# pcb.net
KiCad netlist of a schematic drawn in EAGLE
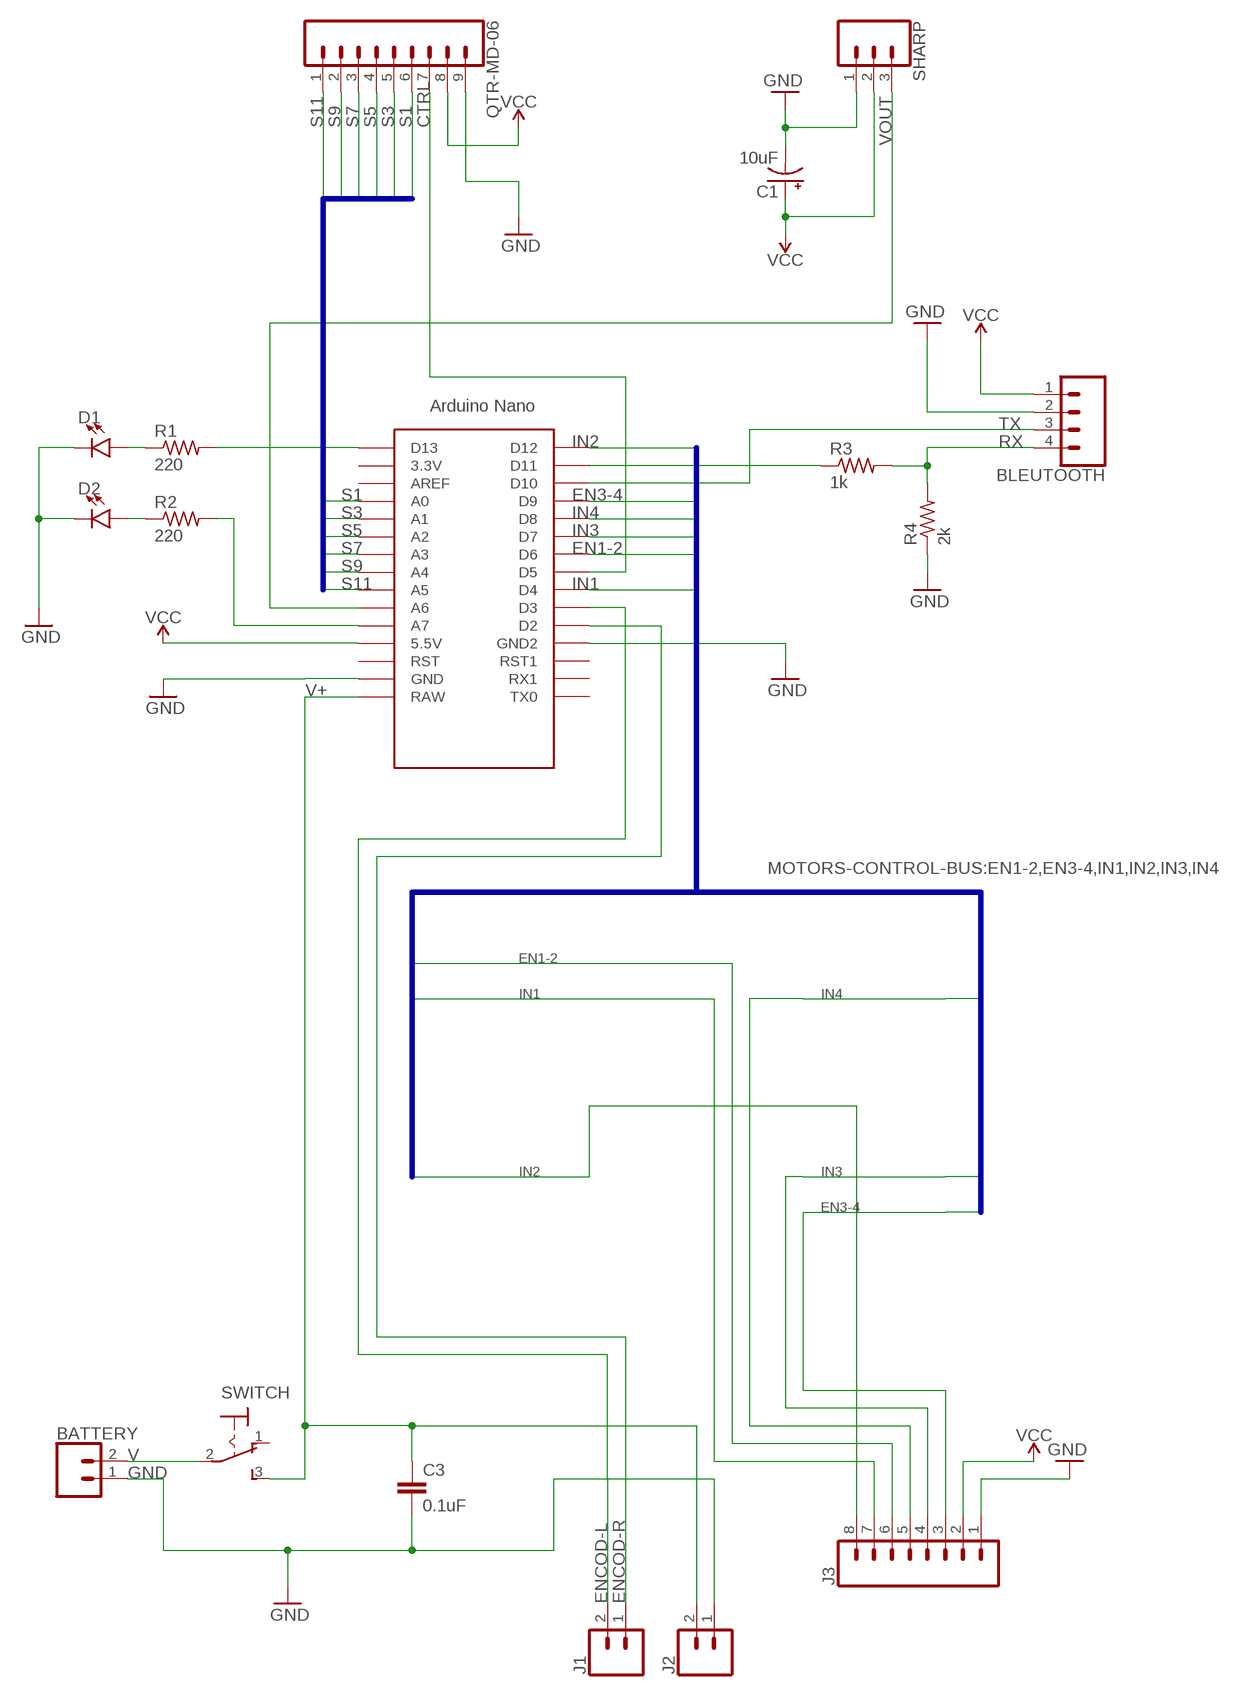
[diagram p0: schematic, sheet 1]

(export (version "E")
  (design (tool "Eeschema 10.0.6"))
  (components
    (comp (ref "BATTERY")
      (value "CONN_02")
      (footprint "eagle-import:1X02")
      (libsource (lib "eagle-import") (part "CONN_02"))
    )
    (comp (ref "BLEUTOOTH")
      (value "CONN_04")
      (footprint "eagle-import:1X04")
      (libsource (lib "eagle-import") (part "CONN_04"))
    )
    (comp (ref "C1")
      (value "10uF")
      (footprint "eagle-import:CPOL-RADIAL-2.5MM-5MM")
      (libsource (lib "eagle-import") (part "10UF-POLAR-RADIAL-2.5MM-25V-20%"))
    )
    (comp (ref "C3")
      (value "0.1uF")
      (footprint "eagle-import:CAP-PTH-SMALL-KIT")
      (libsource (lib "eagle-import") (part "0.1UF-KIT-EZ-50V-20%"))
    )
    (comp (ref "D1")
      (value "LED3MM")
      (footprint "eagle-import:LED_3MM")
      (libsource (lib "eagle-import") (part "LED3MM"))
    )
    (comp (ref "D2")
      (value "LED3MM")
      (footprint "eagle-import:LED_3MM")
      (libsource (lib "eagle-import") (part "LED3MM"))
    )
    (comp (ref "J1")
      (value "CONN_025MM")
      (footprint "eagle-import:SCREWTERMINAL-5MM-2")
      (libsource (lib "eagle-import") (part "CONN_025MM"))
    )
    (comp (ref "J2")
      (value "CONN_025MM")
      (footprint "eagle-import:SCREWTERMINAL-5MM-2")
      (libsource (lib "eagle-import") (part "CONN_025MM"))
    )
    (comp (ref "J3")
      (value "CONN_08\"")
      (footprint "eagle-import:1X08")
      (libsource (lib "eagle-import") (part "CONN_08{dblquote}"))
    )
    (comp (ref "QTR-MD-06")
      (value "CONN_09")
      (footprint "eagle-import:1X09")
      (libsource (lib "eagle-import") (part "CONN_09"))
    )
    (comp (ref "R1")
      (value "220")
      (footprint "eagle-import:0207_12")
      (libsource (lib "eagle-import") (part "R-US_0207/12"))
    )
    (comp (ref "R2")
      (value "220")
      (footprint "eagle-import:0207_12")
      (libsource (lib "eagle-import") (part "R-US_0207/12"))
    )
    (comp (ref "R3")
      (value "1k")
      (footprint "eagle-import:0207_12")
      (libsource (lib "eagle-import") (part "R-US_0207/12"))
    )
    (comp (ref "R4")
      (value "2k")
      (footprint "eagle-import:0207_12")
      (libsource (lib "eagle-import") (part "R-US_0207/12"))
    )
    (comp (ref "SHARP")
      (value "CONN_03")
      (footprint "eagle-import:1X03")
      (libsource (lib "eagle-import") (part "CONN_03"))
    )
    (comp (ref "SWITCH")
      (value "320-916")
      (footprint "eagle-import:320-916")
      (libsource (lib "eagle-import") (part "320-916"))
    )
    (comp (ref "U$1")
      (value "NANO")
      (footprint "eagle-import:NANO")
      (libsource (lib "eagle-import") (part "NANO"))
    )
  )
  (nets
    (net (code "2") (name "/CTRL") (class "Default")
      (node (ref "QTR-MD-06") (pin "7") (pinfunction "7_7") (pintype "passive"))
      (node (ref "U$1") (pin "D5") (pinfunction "D5_D5") (pintype "bidirectional"))
    )
    (net (code "3") (name "/EN1-2") (class "Default")
      (node (ref "J3") (pin "6") (pinfunction "6_6") (pintype "passive"))
      (node (ref "U$1") (pin "D6") (pinfunction "D6_D6") (pintype "bidirectional"))
    )
    (net (code "4") (name "/EN3-4") (class "Default")
      (node (ref "J3") (pin "3") (pinfunction "3_3") (pintype "passive"))
      (node (ref "U$1") (pin "D9") (pinfunction "D9_D9") (pintype "bidirectional"))
    )
    (net (code "5") (name "/ENCOD-L") (class "Default")
      (node (ref "J1") (pin "2") (pinfunction "2_2") (pintype "passive"))
      (node (ref "U$1") (pin "D3") (pinfunction "D3_D3") (pintype "bidirectional"))
    )
    (net (code "6") (name "/ENCOD-R") (class "Default")
      (node (ref "J1") (pin "1") (pinfunction "1_1") (pintype "passive"))
      (node (ref "U$1") (pin "D2") (pinfunction "D2_D2") (pintype "bidirectional"))
    )
    (net (code "7") (name "/IN1") (class "Default")
      (node (ref "J3") (pin "7") (pinfunction "7_7") (pintype "passive"))
      (node (ref "U$1") (pin "D4") (pinfunction "D4_D4") (pintype "bidirectional"))
    )
    (net (code "8") (name "/IN2") (class "Default")
      (node (ref "J3") (pin "8") (pinfunction "8_8") (pintype "passive"))
      (node (ref "U$1") (pin "D12") (pinfunction "D12_D12") (pintype "bidirectional"))
    )
    (net (code "9") (name "/IN3") (class "Default")
      (node (ref "J3") (pin "4") (pinfunction "4_4") (pintype "passive"))
      (node (ref "U$1") (pin "D7") (pinfunction "D7_D7") (pintype "bidirectional"))
    )
    (net (code "10") (name "/IN4") (class "Default")
      (node (ref "J3") (pin "5") (pinfunction "5_5") (pintype "passive"))
      (node (ref "U$1") (pin "D8") (pinfunction "D8_D8") (pintype "bidirectional"))
    )
    (net (code "11") (name "/RX") (class "Default")
      (node (ref "BLEUTOOTH") (pin "4") (pinfunction "4_4") (pintype "passive"))
      (node (ref "R3") (pin "2") (pinfunction "2_2") (pintype "passive"))
      (node (ref "R4") (pin "2") (pinfunction "2_2") (pintype "passive"))
    )
    (net (code "12") (name "/S1") (class "Default")
      (node (ref "QTR-MD-06") (pin "6") (pinfunction "6_6") (pintype "passive"))
      (node (ref "U$1") (pin "A0") (pinfunction "A0_A0") (pintype "bidirectional"))
    )
    (net (code "13") (name "/S3") (class "Default")
      (node (ref "QTR-MD-06") (pin "5") (pinfunction "5_5") (pintype "passive"))
      (node (ref "U$1") (pin "A1") (pinfunction "A1_A1") (pintype "bidirectional"))
    )
    (net (code "14") (name "/S5") (class "Default")
      (node (ref "QTR-MD-06") (pin "4") (pinfunction "4_4") (pintype "passive"))
      (node (ref "U$1") (pin "A2") (pinfunction "A2_A2") (pintype "bidirectional"))
    )
    (net (code "15") (name "/S7") (class "Default")
      (node (ref "QTR-MD-06") (pin "3") (pinfunction "3_3") (pintype "passive"))
      (node (ref "U$1") (pin "A3") (pinfunction "A3_A3") (pintype "bidirectional"))
    )
    (net (code "16") (name "/S9") (class "Default")
      (node (ref "QTR-MD-06") (pin "2") (pinfunction "2_2") (pintype "passive"))
      (node (ref "U$1") (pin "A4") (pinfunction "A4_A4") (pintype "bidirectional"))
    )
    (net (code "17") (name "/S11") (class "Default")
      (node (ref "QTR-MD-06") (pin "1") (pinfunction "1_1") (pintype "passive"))
      (node (ref "U$1") (pin "A5") (pinfunction "A5_A5") (pintype "bidirectional"))
    )
    (net (code "18") (name "/TX") (class "Default")
      (node (ref "BLEUTOOTH") (pin "3") (pinfunction "3_3") (pintype "passive"))
      (node (ref "U$1") (pin "D10") (pinfunction "D10_D10") (pintype "bidirectional"))
    )
    (net (code "19") (name "/V") (class "Default")
      (node (ref "BATTERY") (pin "2") (pinfunction "2_2") (pintype "passive"))
      (node (ref "SWITCH") (pin "2") (pinfunction "P_2") (pintype "passive"))
    )
    (net (code "20") (name "/V+") (class "Default")
      (node (ref "C3") (pin "1") (pinfunction "1_1") (pintype "passive"))
      (node (ref "J2") (pin "2") (pinfunction "2_2") (pintype "passive"))
      (node (ref "SWITCH") (pin "3") (pinfunction "S_3") (pintype "passive"))
      (node (ref "U$1") (pin "RAW") (pinfunction "RAW_RAW") (pintype "bidirectional"))
    )
    (net (code "21") (name "/VOUT") (class "Default")
      (node (ref "SHARP") (pin "3") (pinfunction "3_3") (pintype "passive"))
      (node (ref "U$1") (pin "A6") (pinfunction "A6_A6") (pintype "bidirectional"))
    )
    (net (code "23") (name "GND") (class "Default")
      (node (ref "BATTERY") (pin "1") (pinfunction "1_1") (pintype "passive"))
      (node (ref "BLEUTOOTH") (pin "2") (pinfunction "2_2") (pintype "passive"))
      (node (ref "C1") (pin "2") (pinfunction "-_2") (pintype "passive"))
      (node (ref "C3") (pin "2") (pinfunction "2_2") (pintype "passive"))
      (node (ref "D1") (pin "K") (pinfunction "C_K") (pintype "passive"))
      (node (ref "D2") (pin "K") (pinfunction "C_K") (pintype "passive"))
      (node (ref "J2") (pin "1") (pinfunction "1_1") (pintype "passive"))
      (node (ref "J3") (pin "1") (pinfunction "1_1") (pintype "passive"))
      (node (ref "QTR-MD-06") (pin "9") (pinfunction "9_9") (pintype "passive"))
      (node (ref "R4") (pin "1") (pinfunction "1_1") (pintype "passive"))
      (node (ref "SHARP") (pin "1") (pinfunction "1_1") (pintype "passive"))
      (node (ref "U$1") (pin "GND") (pinfunction "GND_GND") (pintype "bidirectional"))
      (node (ref "U$1") (pin "GND1") (pinfunction "GND2_GND1") (pintype "bidirectional"))
    )
    (net (code "24") (name "Net-(D1-PadA)") (class "Default")
      (node (ref "D1") (pin "A") (pinfunction "A_A") (pintype "passive"))
      (node (ref "R1") (pin "1") (pinfunction "1_1") (pintype "passive"))
    )
    (net (code "25") (name "Net-(D2-PadA)") (class "Default")
      (node (ref "D2") (pin "A") (pinfunction "A_A") (pintype "passive"))
      (node (ref "R2") (pin "1") (pinfunction "1_1") (pintype "passive"))
    )
    (net (code "26") (name "Net-(R1-Pad2)") (class "Default")
      (node (ref "R1") (pin "2") (pinfunction "2_2") (pintype "passive"))
      (node (ref "U$1") (pin "D13") (pinfunction "D13_D13") (pintype "bidirectional"))
    )
    (net (code "27") (name "Net-(R2-Pad2)") (class "Default")
      (node (ref "R2") (pin "2") (pinfunction "2_2") (pintype "passive"))
      (node (ref "U$1") (pin "A7") (pinfunction "A7_A7") (pintype "bidirectional"))
    )
    (net (code "28") (name "Net-(R3-Pad1)") (class "Default")
      (node (ref "R3") (pin "1") (pinfunction "1_1") (pintype "passive"))
      (node (ref "U$1") (pin "D11") (pinfunction "D11_D11") (pintype "bidirectional"))
    )
    (net (code "29") (name "VCC") (class "Default")
      (node (ref "BLEUTOOTH") (pin "1") (pinfunction "1_1") (pintype "passive"))
      (node (ref "C1") (pin "1") (pinfunction "+_1") (pintype "passive"))
      (node (ref "J3") (pin "2") (pinfunction "2_2") (pintype "passive"))
      (node (ref "QTR-MD-06") (pin "8") (pinfunction "8_8") (pintype "passive"))
      (node (ref "SHARP") (pin "2") (pinfunction "2_2") (pintype "passive"))
      (node (ref "U$1") (pin "5V") (pinfunction "5.5V_5V") (pintype "bidirectional"))
    )
    (net (code "30") (name "unconnected-(SWITCH-O-Pad1)") (class "Default")
      (node (ref "SWITCH") (pin "1") (pinfunction "O_1") (pintype "passive"))
    )
    (net (code "31") (name "unconnected-(U$1-Pad3.3V)") (class "Default")
      (node (ref "U$1") (pin "3.3V") (pinfunction "3.3V_3.3V") (pintype "bidirectional"))
    )
    (net (code "32") (name "unconnected-(U$1-PadAREF)") (class "Default")
      (node (ref "U$1") (pin "AREF") (pinfunction "AREF_AREF") (pintype "bidirectional"))
    )
    (net (code "33") (name "unconnected-(U$1-PadICSP1)") (class "Default")
      (node (ref "U$1") (pin "ICSP1") (pinfunction "ICSP1_ICSP1") (pintype "bidirectional"))
    )
    (net (code "34") (name "unconnected-(U$1-PadICSP2)") (class "Default")
      (node (ref "U$1") (pin "ICSP2") (pinfunction "ICSP2_ICSP2") (pintype "bidirectional"))
    )
    (net (code "35") (name "unconnected-(U$1-PadICSP3)") (class "Default")
      (node (ref "U$1") (pin "ICSP3") (pinfunction "ICSP3_ICSP3") (pintype "bidirectional"))
    )
    (net (code "36") (name "unconnected-(U$1-PadICSP4)") (class "Default")
      (node (ref "U$1") (pin "ICSP4") (pinfunction "ICSP4_ICSP4") (pintype "bidirectional"))
    )
    (net (code "37") (name "unconnected-(U$1-PadICSP5)") (class "Default")
      (node (ref "U$1") (pin "ICSP5") (pinfunction "ICSP5_ICSP5") (pintype "bidirectional"))
    )
    (net (code "38") (name "unconnected-(U$1-PadICSP6)") (class "Default")
      (node (ref "U$1") (pin "ICSP6") (pinfunction "ICSP6_ICSP6") (pintype "bidirectional"))
    )
    (net (code "39") (name "unconnected-(U$1-PadRST)") (class "Default")
      (node (ref "U$1") (pin "RST") (pinfunction "RST_RST") (pintype "bidirectional"))
    )
    (net (code "40") (name "unconnected-(U$1-PadRST1)") (class "Default")
      (node (ref "U$1") (pin "RST1") (pinfunction "RST1_RST1") (pintype "bidirectional"))
    )
    (net (code "41") (name "unconnected-(U$1-PadRX1)") (class "Default")
      (node (ref "U$1") (pin "RX1") (pinfunction "RX1_RX1") (pintype "bidirectional"))
    )
    (net (code "42") (name "unconnected-(U$1-PadTX0)") (class "Default")
      (node (ref "U$1") (pin "TX0") (pinfunction "TX0_TX0") (pintype "bidirectional"))
    )
  )
)
